# -USBasp_v1_1.net
KiCad netlist of a schematic drawn in EAGLE
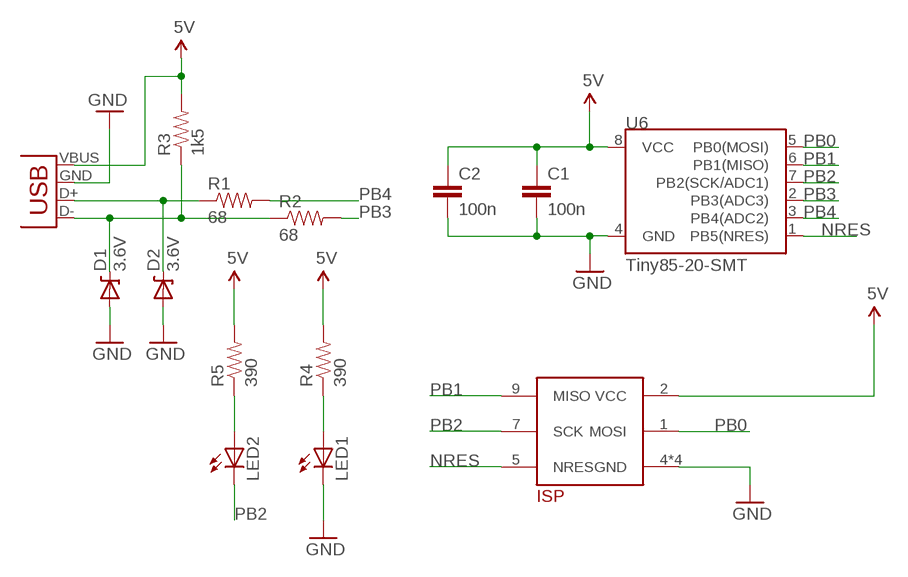
[diagram p0: schematic, sheet 1]

(export (version "E")
  (design (tool "Eeschema 10.0.6"))
  (components
    (comp (ref "C1")
      (value "100n")
      (footprint "eagle-import:0805")
      (libsource (lib "eagle-import") (part "CAP0805"))
    )
    (comp (ref "C2")
      (value "100n")
      (footprint "eagle-import:0805")
      (libsource (lib "eagle-import") (part "CAP0805"))
    )
    (comp (ref "D1")
      (value "3.6V")
      (footprint "eagle-import:SOD-323")
      (libsource (lib "eagle-import") (part "DIODE-ZENER-BZT52"))
    )
    (comp (ref "D2")
      (value "3.6V")
      (footprint "eagle-import:SOD-323")
      (libsource (lib "eagle-import") (part "DIODE-ZENER-BZT52"))
    )
    (comp (ref "JP2")
      (value "USB-A-H")
      (footprint "eagle-import:USB-A-H")
      (libsource (lib "eagle-import") (part "USB-A-H"))
    )
    (comp (ref "LED1")
      (value "LEDCHIPLED_0805")
      (footprint "eagle-import:CHIPLED_0805")
      (libsource (lib "eagle-import") (part "LEDCHIPLED_0805"))
    )
    (comp (ref "LED2")
      (value "LEDCHIPLED_0805")
      (footprint "eagle-import:CHIPLED_0805")
      (libsource (lib "eagle-import") (part "LEDCHIPLED_0805"))
    )
    (comp (ref "R1")
      (value "68")
      (footprint "eagle-import:0805")
      (libsource (lib "eagle-import") (part "RESISTOR0805-RES"))
    )
    (comp (ref "R2")
      (value "68")
      (footprint "eagle-import:0805")
      (libsource (lib "eagle-import") (part "RESISTOR0805-RES"))
    )
    (comp (ref "R3")
      (value "1k5")
      (footprint "eagle-import:0805")
      (libsource (lib "eagle-import") (part "RESISTOR0805-RES"))
    )
    (comp (ref "R4")
      (value "390")
      (footprint "eagle-import:0805")
      (libsource (lib "eagle-import") (part "RESISTOR0805-RES"))
    )
    (comp (ref "R5")
      (value "390")
      (footprint "eagle-import:0805")
      (libsource (lib "eagle-import") (part "RESISTOR0805-RES"))
    )
    (comp (ref "U$1")
      (value "TB_ISPEDGE_2X5_LONG")
      (footprint "eagle-import:ISP_EDGE2X5_LONG")
      (libsource (lib "eagle-import") (part "TB_ISPEDGE_2X5_LONG"))
    )
    (comp (ref "U6")
      (value "Tiny85-20-SMT")
      (footprint "eagle-import:SO08-EIAJ")
      (libsource (lib "eagle-import") (part "ATTINY45TINY85-20-SMT"))
    )
  )
  (nets
    (net (code "1") (name "/NRES") (class "Default")
      (node (ref "U$1") (pin "5") (pinfunction "NRES_5") (pintype "bidirectional"))
      (node (ref "U6") (pin "1") (pinfunction "PB5(NRES)_1") (pintype "bidirectional"))
    )
    (net (code "2") (name "/PB0") (class "Default")
      (node (ref "U$1") (pin "1") (pinfunction "MOSI_1") (pintype "bidirectional"))
      (node (ref "U6") (pin "5") (pinfunction "PB0(MOSI)_5") (pintype "bidirectional"))
    )
    (net (code "3") (name "/PB1") (class "Default")
      (node (ref "U$1") (pin "9") (pinfunction "MISO_9") (pintype "bidirectional"))
      (node (ref "U6") (pin "6") (pinfunction "PB1(MISO)_6") (pintype "bidirectional"))
    )
    (net (code "4") (name "/PB2") (class "Default")
      (node (ref "LED2") (pin "C") (pinfunction "C_C") (pintype "passive"))
      (node (ref "U$1") (pin "7") (pinfunction "SCK_7") (pintype "bidirectional"))
      (node (ref "U6") (pin "7") (pinfunction "PB2(SCK/ADC1)_7") (pintype "bidirectional"))
    )
    (net (code "5") (name "/PB3") (class "Default")
      (node (ref "R2") (pin "2") (pinfunction "2_2") (pintype "passive"))
      (node (ref "U6") (pin "2") (pinfunction "PB3(ADC3)_2") (pintype "bidirectional"))
    )
    (net (code "6") (name "/PB4") (class "Default")
      (node (ref "R1") (pin "2") (pinfunction "2_2") (pintype "passive"))
      (node (ref "U6") (pin "3") (pinfunction "PB4(ADC2)_3") (pintype "bidirectional"))
    )
    (net (code "7") (name "5V") (class "Default")
      (node (ref "C1") (pin "1") (pinfunction "1_1") (pintype "passive"))
      (node (ref "C2") (pin "1") (pinfunction "1_1") (pintype "passive"))
      (node (ref "JP2") (pin "VBUS") (pinfunction "GND_VBUS") (pintype "bidirectional"))
      (node (ref "R3") (pin "2") (pinfunction "2_2") (pintype "passive"))
      (node (ref "R4") (pin "2") (pinfunction "2_2") (pintype "passive"))
      (node (ref "R5") (pin "2") (pinfunction "2_2") (pintype "passive"))
      (node (ref "U$1") (pin "2") (pinfunction "VCC_2") (pintype "bidirectional"))
      (node (ref "U6") (pin "8") (pinfunction "VCC_8") (pintype "bidirectional"))
    )
    (net (code "8") (name "GND") (class "Default")
      (node (ref "C1") (pin "2") (pinfunction "2_2") (pintype "passive"))
      (node (ref "C2") (pin "2") (pinfunction "2_2") (pintype "passive"))
      (node (ref "D1") (pin "2") (pinfunction "A_2") (pintype "passive"))
      (node (ref "D2") (pin "2") (pinfunction "A_2") (pintype "passive"))
      (node (ref "JP2") (pin "GND") (pinfunction "VBUS_GND") (pintype "bidirectional"))
      (node (ref "LED1") (pin "C") (pinfunction "C_C") (pintype "passive"))
      (node (ref "U$1") (pin "10") (pinfunction "GND_10") (pintype "bidirectional"))
      (node (ref "U$1") (pin "4") (pinfunction "GND_4") (pintype "bidirectional"))
      (node (ref "U$1") (pin "6") (pinfunction "GND_6") (pintype "bidirectional"))
      (node (ref "U$1") (pin "8") (pinfunction "GND_8") (pintype "bidirectional"))
      (node (ref "U6") (pin "4") (pinfunction "GND_4") (pintype "bidirectional"))
    )
    (net (code "9") (name "Net-(D1-C)") (class "Default")
      (node (ref "D1") (pin "1") (pinfunction "C_1") (pintype "passive"))
      (node (ref "JP2") (pin "D-") (pinfunction "D+_D-") (pintype "bidirectional"))
      (node (ref "R2") (pin "1") (pinfunction "1_1") (pintype "passive"))
      (node (ref "R3") (pin "1") (pinfunction "1_1") (pintype "passive"))
    )
    (net (code "10") (name "Net-(D2-C)") (class "Default")
      (node (ref "D2") (pin "1") (pinfunction "C_1") (pintype "passive"))
      (node (ref "JP2") (pin "D+") (pinfunction "D-_D+") (pintype "bidirectional"))
      (node (ref "R1") (pin "1") (pinfunction "1_1") (pintype "passive"))
    )
    (net (code "11") (name "Net-(LED1-PadA)") (class "Default")
      (node (ref "LED1") (pin "A") (pinfunction "A_A") (pintype "passive"))
      (node (ref "R4") (pin "1") (pinfunction "1_1") (pintype "passive"))
    )
    (net (code "12") (name "Net-(LED2-PadA)") (class "Default")
      (node (ref "LED2") (pin "A") (pinfunction "A_A") (pintype "passive"))
      (node (ref "R5") (pin "1") (pinfunction "1_1") (pintype "passive"))
    )
  )
)
